# Sheet1.net
KiCad netlist of a schematic drawn in Altium Designer
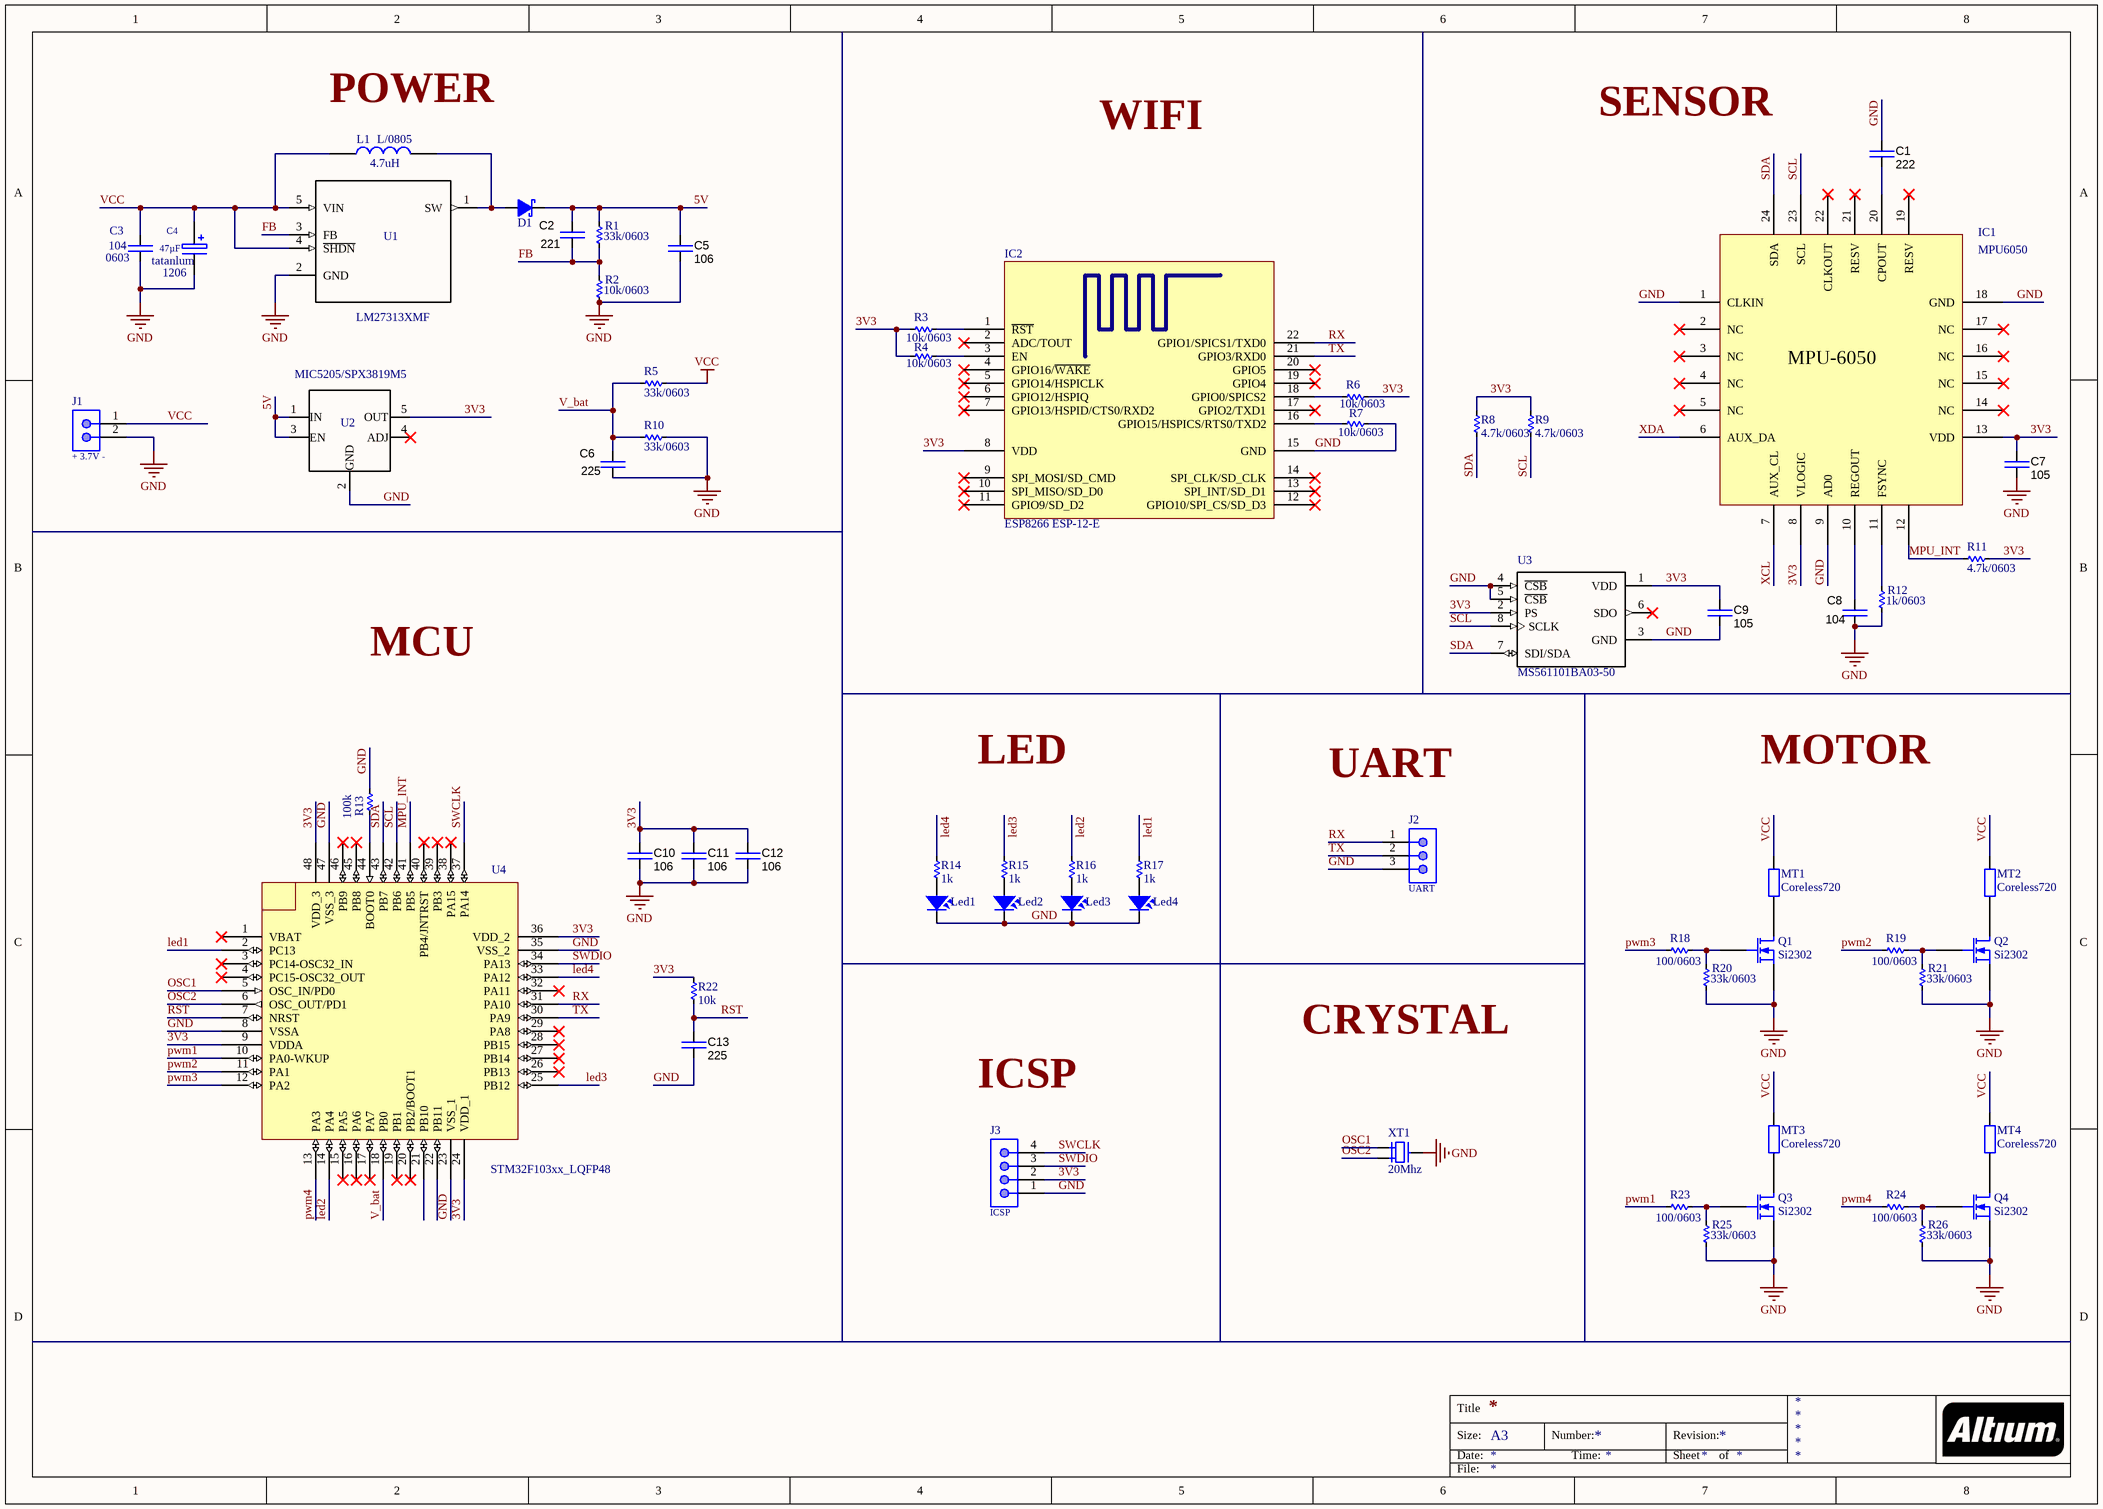
[diagram p0: Sheet1.SchDoc]

(export (version "E")
  (design (tool "Eeschema 10.0.6"))
  (components
    (comp (ref "C1")
      (value "222")
      (footprint "my Library:CAPC1608X90N")
      (description "Capacitor SMD Cer 470nF 10% 16V X7R 0603")
      (fields (field (name "TOLERANCE") "±10%"))
      (libsource (lib "my Library") (part "CAP C_0603"))
    )
    (comp (ref "C2")
      (value "221")
      (footprint "my Library:CAPC1608X90N")
      (description "Capacitor SMD Cer 470nF 10% 16V X7R 0603")
      (fields (field (name "TOLERANCE") "±10%"))
      (libsource (lib "my Library") (part "CAP C_0603"))
    )
    (comp (ref "C3")
      (value "104")
      (footprint "CAPC1608X90N")
      (description "Capacitor SMD 224/0603, Addr:Linhkien69.vn")
      (fields (field (name "PACKAGE / CASE") "0603") (field (name "TOLERANCE") "±10%"))
      (libsource (lib "My library altium") (part "CAP C_0603"))
    )
    (comp (ref "C4")
      (value "tatanlum")
      (footprint "CM_S_1206")
      (description "Tatalium SMD 47uf/1206, Addr:Linhkien69.vn")
      (fields (field (name "ALTIUM_UNNAMED_1") "47µF") (field (name "SIZE") "1206"))
      (libsource (lib "My library altium") (part "CAP Tatalium"))
    )
    (comp (ref "C5")
      (value "106")
      (footprint "my Library:CAPC1608X90N")
      (description "Capacitor SMD Cer 470nF 10% 16V X7R 0603")
      (fields (field (name "TOLERANCE") "±10%"))
      (libsource (lib "my Library") (part "CAP C_0603"))
    )
    (comp (ref "C6")
      (value "225")
      (footprint "my Library:CAPC1608X90N")
      (description "Capacitor SMD Cer 470nF 10% 16V X7R 0603")
      (fields (field (name "TOLERANCE") "±10%"))
      (libsource (lib "my Library") (part "CAP C_0603"))
    )
    (comp (ref "C7")
      (value "105")
      (footprint "my Library:CAPC1608X90N")
      (description "Capacitor SMD Cer 470nF 10% 16V X7R 0603")
      (fields (field (name "TOLERANCE") "±10%"))
      (libsource (lib "my Library") (part "CAP C_0603"))
    )
    (comp (ref "C8")
      (value "104")
      (footprint "my Library:CAPC1608X90N")
      (description "Capacitor SMD Cer 470nF 10% 16V X7R 0603")
      (fields (field (name "TOLERANCE") "±10%"))
      (libsource (lib "my Library") (part "CAP C_0603"))
    )
    (comp (ref "C9")
      (value "105")
      (footprint "my Library:CAPC1608X90N")
      (description "Capacitor SMD Cer 470nF 10% 16V X7R 0603")
      (fields (field (name "TOLERANCE") "±10%"))
      (libsource (lib "my Library") (part "CAP C_0603"))
    )
    (comp (ref "C10")
      (value "106")
      (footprint "my Library:CAPC1608X90N")
      (description "Capacitor SMD Cer 470nF 10% 16V X7R 0603")
      (fields (field (name "TOLERANCE") "±10%"))
      (libsource (lib "my Library") (part "CAP C_0603"))
    )
    (comp (ref "C11")
      (value "106")
      (footprint "my Library:CAPC1608X90N")
      (description "Capacitor SMD Cer 470nF 10% 16V X7R 0603")
      (fields (field (name "TOLERANCE") "±10%"))
      (libsource (lib "my Library") (part "CAP C_0603"))
    )
    (comp (ref "C12")
      (value "106")
      (footprint "my Library:CAPC1608X90N")
      (description "Capacitor SMD Cer 470nF 10% 16V X7R 0603")
      (fields (field (name "TOLERANCE") "±10%"))
      (libsource (lib "my Library") (part "CAP C_0603"))
    )
    (comp (ref "C13")
      (value "225")
      (footprint "my Library:CAPC1608X90N")
      (description "Capacitor SMD Cer 470nF 10% 16V X7R 0603")
      (fields (field (name "TOLERANCE") "±10%"))
      (libsource (lib "my Library") (part "CAP C_0603"))
    )
    (comp (ref "D1")
      (value "Diode  Schottky 1N5819")
      (footprint "DO-214AC")
      (description "Diode SS24 SMD 0805, Addr:Linhkien69.vn")
      (libsource (lib "My library altium") (part "Diode  Schottky 1N5819"))
    )
    (comp (ref "IC1")
      (value "MPU6050")
      (footprint "MPU6050")
      (description "Addr:Banlinhkien.vn")
      (libsource (lib "My library altium") (part "MPU6050"))
    )
    (comp (ref "IC2")
      (value "ESP8266 ESP-12-E")
      (footprint "ESP8266:ESP8266 ESP-12-E")
      (libsource (lib "ESP8266") (part "ESP8266 ESP-12-E"))
    )
    (comp (ref "J1")
      (value "+ 3.7V -")
      (footprint "62000211121")
      (description "WR-PHD Pin Header, THT, pitch 2mm, Single Row, Vertical, 2pin")
      (fields (field (name "PART NUMBER") "62000211121") (field (name "PUBLISHER") "Wurth Elektronik"))
      (libsource (lib "o155175v243 Altium_WR-PHD (rev19a)") (part "62000211121"))
    )
    (comp (ref "J2")
      (value "UART")
      (footprint "62000311121")
      (description "WR-PHD Pin Header, THT, pitch 2mm, Single Row, Vertical, 3pin")
      (fields (field (name "PART NUMBER") "62000311121") (field (name "PUBLISHER") "Wurth Elektronik"))
      (libsource (lib "o155175v243 Altium_WR-PHD (rev19a)") (part "62000311121"))
    )
    (comp (ref "J3")
      (value "ICSP")
      (footprint "62000411121")
      (description "WR-PHD Pin Header, THT, pitch 2mm, Single Row, Vertical, 4pin")
      (fields (field (name "PART NUMBER") "62000411121") (field (name "PUBLISHER") "Wurth Elektronik"))
      (libsource (lib "o155175v243 Altium_WR-PHD (rev19a)") (part "62000411121"))
    )
    (comp (ref "L1")
      (value "L/0805")
      (footprint "SM-IND-0805")
      (description "Inductor SMD 4.7uH/0805, Addr:Linhkien69.vn")
      (fields (field (name "ALTIUM_VALUE") "4.7uH"))
      (libsource (lib "My library altium") (part "Inductor Iron"))
    )
    (comp (ref "Led1")
      (value "LED")
      (footprint "LED-0805-Red")
      (description "LED SMD0805                Addr:Linhkien69.vn")
      (libsource (lib "LIBRARY") (part "LED SMD"))
    )
    (comp (ref "Led2")
      (value "LED")
      (footprint "LED-0805-Red")
      (description "LED SMD0805                Addr:Linhkien69.vn")
      (libsource (lib "LIBRARY") (part "LED SMD"))
    )
    (comp (ref "Led3")
      (value "LED")
      (footprint "LED-0805-Red")
      (description "LED SMD0805                Addr:Linhkien69.vn")
      (libsource (lib "LIBRARY") (part "LED SMD"))
    )
    (comp (ref "Led4")
      (value "LED")
      (footprint "LED-0805-Red")
      (description "LED SMD0805                Addr:Linhkien69.vn")
      (libsource (lib "LIBRARY") (part "LED SMD"))
    )
    (comp (ref "MT1")
      (value "Coreless720")
      (footprint "SM-0805")
      (description "Resistor SMD")
      (libsource (lib "syhaunguyen") (part "RM"))
    )
    (comp (ref "MT2")
      (value "Coreless720")
      (footprint "SM-0805")
      (description "Resistor SMD")
      (libsource (lib "syhaunguyen") (part "RM"))
    )
    (comp (ref "MT3")
      (value "Coreless720")
      (footprint "SM-0805")
      (description "Resistor SMD")
      (libsource (lib "syhaunguyen") (part "RM"))
    )
    (comp (ref "MT4")
      (value "Coreless720")
      (footprint "SM-0805")
      (description "Resistor SMD")
      (libsource (lib "syhaunguyen") (part "RM"))
    )
    (comp (ref "Q1")
      (value "Si2302")
      (footprint "SOT23")
      (description "Transistor SMD            Addr:Banlinhkien.vn")
      (fields (field (name "PUBLISHER") "Altium Limited"))
      (libsource (lib "My library altium") (part "Si2302DS"))
    )
    (comp (ref "Q2")
      (value "Si2302")
      (footprint "SOT23")
      (description "Transistor SMD            Addr:Banlinhkien.vn")
      (fields (field (name "PUBLISHER") "Altium Limited"))
      (libsource (lib "My library altium") (part "Si2302DS"))
    )
    (comp (ref "Q3")
      (value "Si2302")
      (footprint "SOT23")
      (description "Transistor SMD            Addr:Banlinhkien.vn")
      (fields (field (name "PUBLISHER") "Altium Limited"))
      (libsource (lib "My library altium") (part "Si2302DS"))
    )
    (comp (ref "Q4")
      (value "Si2302")
      (footprint "SOT23")
      (description "Transistor SMD            Addr:Banlinhkien.vn")
      (fields (field (name "PUBLISHER") "Altium Limited"))
      (libsource (lib "My library altium") (part "Si2302DS"))
    )
    (comp (ref "R1")
      (value "33k/0603")
      (footprint "RES-SMD-0603")
      (description "Resistor SMD 33k/0603, Addr:Linhkien69.vn")
      (fields
        (field (name "MANUFACTURER") "Generic Components")
        (field (name "PUBLISHER") "Altium Hobart Technology Centre")
      )
      (libsource (lib "LIBRARY") (part "Res-SMD"))
    )
    (comp (ref "R2")
      (value "10k/0603")
      (footprint "RES-SMD-0603")
      (description "Resistor SMD 10k/0603, Addr:Linhkien69.vn")
      (fields
        (field (name "MANUFACTURER") "Generic Components")
        (field (name "PUBLISHER") "Altium Hobart Technology Centre")
      )
      (libsource (lib "LIBRARY") (part "Res-SMD"))
    )
    (comp (ref "R3")
      (value "10k/0603")
      (footprint "RES-SMD-0603")
      (description "Resistor SMD 4.7k/0603, Addr:Linhkien69.vn")
      (fields
        (field (name "MANUFACTURER") "Generic Components")
        (field (name "PUBLISHER") "Altium Hobart Technology Centre")
      )
      (libsource (lib "LIBRARY") (part "Res-SMD"))
    )
    (comp (ref "R4")
      (value "10k/0603")
      (footprint "RES-SMD-0603")
      (description "Resistor SMD 4.7k/0603, Addr:Linhkien69.vn")
      (fields
        (field (name "MANUFACTURER") "Generic Components")
        (field (name "PUBLISHER") "Altium Hobart Technology Centre")
      )
      (libsource (lib "LIBRARY") (part "Res-SMD"))
    )
    (comp (ref "R5")
      (value "33k/0603")
      (footprint "RES-SMD-0603")
      (description "Resistor SMD 33k/0603, Addr:Linhkien69.vn")
      (fields
        (field (name "MANUFACTURER") "Generic Components")
        (field (name "PUBLISHER") "Altium Hobart Technology Centre")
      )
      (libsource (lib "LIBRARY") (part "Res-SMD"))
    )
    (comp (ref "R6")
      (value "10k/0603")
      (footprint "RES-SMD-0603")
      (description "Resistor SMD 4.7k/0603, Addr:Linhkien69.vn")
      (fields
        (field (name "MANUFACTURER") "Generic Components")
        (field (name "PUBLISHER") "Altium Hobart Technology Centre")
      )
      (libsource (lib "LIBRARY") (part "Res-SMD"))
    )
    (comp (ref "R7")
      (value "10k/0603")
      (footprint "RES-SMD-0603")
      (description "Resistor SMD 4.7k/0603, Addr:Linhkien69.vn")
      (fields
        (field (name "MANUFACTURER") "Generic Components")
        (field (name "PUBLISHER") "Altium Hobart Technology Centre")
      )
      (libsource (lib "LIBRARY") (part "Res-SMD"))
    )
    (comp (ref "R8")
      (value "4.7k/0603")
      (footprint "RES-SMD-0603")
      (description "Resistor SMD 4.7k/0603, Addr:Linhkien69.vn")
      (fields
        (field (name "MANUFACTURER") "Generic Components")
        (field (name "PUBLISHER") "Altium Hobart Technology Centre")
      )
      (libsource (lib "LIBRARY") (part "Res-SMD"))
    )
    (comp (ref "R9")
      (value "4.7k/0603")
      (footprint "RES-SMD-0603")
      (description "Resistor SMD 4.7k/0603, Addr:Linhkien69.vn")
      (fields
        (field (name "MANUFACTURER") "Generic Components")
        (field (name "PUBLISHER") "Altium Hobart Technology Centre")
      )
      (libsource (lib "LIBRARY") (part "Res-SMD"))
    )
    (comp (ref "R10")
      (value "33k/0603")
      (footprint "RES-SMD-0603")
      (description "Resistor SMD 33k/0603, Addr:Linhkien69.vn")
      (fields
        (field (name "MANUFACTURER") "Generic Components")
        (field (name "PUBLISHER") "Altium Hobart Technology Centre")
      )
      (libsource (lib "LIBRARY") (part "Res-SMD"))
    )
    (comp (ref "R11")
      (value "4.7k/0603")
      (footprint "RES-SMD-0603")
      (description "Resistor SMD 4.7k/0603, Addr:Linhkien69.vn")
      (fields
        (field (name "MANUFACTURER") "Generic Components")
        (field (name "PUBLISHER") "Altium Hobart Technology Centre")
      )
      (libsource (lib "LIBRARY") (part "Res-SMD"))
    )
    (comp (ref "R12")
      (value "1k/0603")
      (footprint "RES-SMD-0603")
      (description "Resistor SMD 1k/0603, Addr:Linhkien69.vn")
      (fields
        (field (name "MANUFACTURER") "Generic Components")
        (field (name "PUBLISHER") "Altium Hobart Technology Centre")
      )
      (libsource (lib "LIBRARY") (part "Res-SMD"))
    )
    (comp (ref "R13")
      (value "100k")
      (footprint "RES-SMD-0603")
      (description "Resistor")
      (fields
        (field (name "MANUFACTURER") "Generic Components")
        (field (name "PUBLISHER") "Altium Hobart Technology Centre")
      )
      (libsource (lib "LIBRARY") (part "Res-SMD"))
    )
    (comp (ref "R14")
      (value "1k")
      (footprint "RES-SMD-0603")
      (description "Resistor SMD 1k/0603, Addr:Linhkien69.vn")
      (fields
        (field (name "MANUFACTURER") "Generic Components")
        (field (name "PUBLISHER") "Altium Hobart Technology Centre")
      )
      (libsource (lib "LIBRARY") (part "Res-SMD"))
    )
    (comp (ref "R15")
      (value "1k")
      (footprint "RES-SMD-0603")
      (description "Resistor SMD 1k/0603, Addr:Linhkien69.vn")
      (fields
        (field (name "MANUFACTURER") "Generic Components")
        (field (name "PUBLISHER") "Altium Hobart Technology Centre")
      )
      (libsource (lib "LIBRARY") (part "Res-SMD"))
    )
    (comp (ref "R16")
      (value "1k")
      (footprint "RES-SMD-0603")
      (description "Resistor SMD 1k/0603, Addr:Linhkien69.vn")
      (fields
        (field (name "MANUFACTURER") "Generic Components")
        (field (name "PUBLISHER") "Altium Hobart Technology Centre")
      )
      (libsource (lib "LIBRARY") (part "Res-SMD"))
    )
    (comp (ref "R17")
      (value "1k")
      (footprint "RES-SMD-0603")
      (description "Resistor SMD 1k/0603, Addr:Linhkien69.vn")
      (fields
        (field (name "MANUFACTURER") "Generic Components")
        (field (name "PUBLISHER") "Altium Hobart Technology Centre")
      )
      (libsource (lib "LIBRARY") (part "Res-SMD"))
    )
    (comp (ref "R18")
      (value "100/0603")
      (footprint "RES-SMD-0603")
      (description "Resistor SMD 33k/0603, Addr:Linhkien69.vn")
      (fields
        (field (name "MANUFACTURER") "Generic Components")
        (field (name "PUBLISHER") "Altium Hobart Technology Centre")
      )
      (libsource (lib "LIBRARY") (part "Res-SMD"))
    )
    (comp (ref "R19")
      (value "100/0603")
      (footprint "RES-SMD-0603")
      (description "Resistor SMD 33k/0603, Addr:Linhkien69.vn")
      (fields
        (field (name "MANUFACTURER") "Generic Components")
        (field (name "PUBLISHER") "Altium Hobart Technology Centre")
      )
      (libsource (lib "LIBRARY") (part "Res-SMD"))
    )
    (comp (ref "R20")
      (value "33k/0603")
      (footprint "RES-SMD-0603")
      (description "Resistor SMD 33k/0603, Addr:Linhkien69.vn")
      (fields
        (field (name "MANUFACTURER") "Generic Components")
        (field (name "PUBLISHER") "Altium Hobart Technology Centre")
      )
      (libsource (lib "LIBRARY") (part "Res-SMD"))
    )
    (comp (ref "R21")
      (value "33k/0603")
      (footprint "RES-SMD-0603")
      (description "Resistor SMD 33k/0603, Addr:Linhkien69.vn")
      (fields
        (field (name "MANUFACTURER") "Generic Components")
        (field (name "PUBLISHER") "Altium Hobart Technology Centre")
      )
      (libsource (lib "LIBRARY") (part "Res-SMD"))
    )
    (comp (ref "R22")
      (value "10k")
      (footprint "RES-SMD-0603")
      (description "Resistor")
      (fields
        (field (name "MANUFACTURER") "Generic Components")
        (field (name "PUBLISHER") "Altium Hobart Technology Centre")
      )
      (libsource (lib "LIBRARY") (part "Res-SMD"))
    )
    (comp (ref "R23")
      (value "100/0603")
      (footprint "RES-SMD-0603")
      (description "Resistor SMD 33k/0603, Addr:Linhkien69.vn")
      (fields
        (field (name "MANUFACTURER") "Generic Components")
        (field (name "PUBLISHER") "Altium Hobart Technology Centre")
      )
      (libsource (lib "LIBRARY") (part "Res-SMD"))
    )
    (comp (ref "R24")
      (value "100/0603")
      (footprint "RES-SMD-0603")
      (description "Resistor SMD 33k/0603, Addr:Linhkien69.vn")
      (fields
        (field (name "MANUFACTURER") "Generic Components")
        (field (name "PUBLISHER") "Altium Hobart Technology Centre")
      )
      (libsource (lib "LIBRARY") (part "Res-SMD"))
    )
    (comp (ref "R25")
      (value "33k/0603")
      (footprint "RES-SMD-0603")
      (description "Resistor SMD 33k/0603, Addr:Linhkien69.vn")
      (fields
        (field (name "MANUFACTURER") "Generic Components")
        (field (name "PUBLISHER") "Altium Hobart Technology Centre")
      )
      (libsource (lib "LIBRARY") (part "Res-SMD"))
    )
    (comp (ref "R26")
      (value "33k/0603")
      (footprint "RES-SMD-0603")
      (description "Resistor SMD 33k/0603, Addr:Linhkien69.vn")
      (fields
        (field (name "MANUFACTURER") "Generic Components")
        (field (name "PUBLISHER") "Altium Hobart Technology Centre")
      )
      (libsource (lib "LIBRARY") (part "Res-SMD"))
    )
    (comp (ref "U1")
      (value "LM27313XMF")
      (footprint "SOT95P285X120-5N")
      (description "Boost SMD/SOT95,  Addr:Banlinhkien.vn")
      (fields (field (name "MP") "LM27313XMF/NOPB") (field (name "MF") "Texas Instruments"))
      (libsource (lib "LM27313XMF") (part "LM27313XMF"))
    )
    (comp (ref "U2")
      (value "MIC5205/SPX3819M5")
      (footprint "SOT-23-5")
      (description "3.3V SMD/SOT23,    Addr:Banlinhkien.vn")
      (fields (field (name "MP") "MIC5205-3.3YM5 TR") (field (name "MF") "Micrel"))
      (libsource (lib "PMIC-MIC5205-3.3YMSTR_SOT23-5_") (part "PMIC-MIC5205-3.3YMSTR(SOT23-5)"))
    )
    (comp (ref "U3")
      (value "MS561101BA03-50")
      (footprint "SON125P500X300X100-8N")
      (description "Addr:Banlinhkien.vn")
      (fields (field (name "MF") "TE Connectivity"))
      (libsource (lib "MS561101BA03-50") (part "MS561101BA03-50"))
    )
    (comp (ref "U4")
      (value "STM32F103xx_LQFP48")
      (footprint "STM32_LQPF48")
      (description "STM32 ARM-based 32-bit MCU with 64 Kbytes Flash, 48-pin LQFP, Industrial Temperature")
      (fields (field (name "PUBLISHER") "Altium Limited"))
      (libsource (lib "My library altium") (part "STM32F103xx_LQFP48"))
    )
    (comp (ref "XT1")
      (value "20Mhz")
      (footprint "CRYSTAL CSTCE20M0V53-R0")
      (description "Crystal For all Crystal 2pin.")
      (libsource (lib "My library altium") (part "CRYSTAL 3 Chan"))
    )
  )
  (nets
    (net (code "1") (name "/3V3") (class "Default")
      (node (ref "C10") (pin "2") (pintype "passive"))
      (node (ref "C11") (pin "2") (pintype "passive"))
      (node (ref "C12") (pin "2") (pintype "passive"))
      (node (ref "C7") (pin "2") (pintype "passive"))
      (node (ref "C9") (pin "2") (pintype "passive"))
      (node (ref "IC1") (pin "13") (pinfunction "VDD_13") (pintype "passive"))
      (node (ref "IC1") (pin "8") (pinfunction "VLOGIC_8") (pintype "passive"))
      (node (ref "IC2") (pin "8") (pinfunction "VDD_8") (pintype "passive"))
      (node (ref "J3") (pin "2") (pinfunction "2_2") (pintype "passive"))
      (node (ref "R11") (pin "2") (pinfunction "2_2") (pintype "passive"))
      (node (ref "R22") (pin "2") (pinfunction "2_2") (pintype "passive"))
      (node (ref "R3") (pin "2") (pinfunction "2_2") (pintype "passive"))
      (node (ref "R4") (pin "2") (pinfunction "2_2") (pintype "passive"))
      (node (ref "R6") (pin "1") (pinfunction "1_1") (pintype "passive"))
      (node (ref "R8") (pin "2") (pinfunction "2_2") (pintype "passive"))
      (node (ref "R9") (pin "2") (pinfunction "2_2") (pintype "passive"))
      (node (ref "U2") (pin "5") (pinfunction "OUT_5") (pintype "bidirectional"))
      (node (ref "U3") (pin "1") (pinfunction "VDD_1") (pintype "power_in"))
      (node (ref "U3") (pin "2") (pinfunction "PS_2") (pintype "input"))
      (node (ref "U4") (pin "24") (pinfunction "VDD_1_24") (pintype "power_in"))
      (node (ref "U4") (pin "36") (pinfunction "VDD_2_36") (pintype "power_in"))
      (node (ref "U4") (pin "48") (pinfunction "VDD_3_48") (pintype "power_in"))
      (node (ref "U4") (pin "9") (pinfunction "VDDA_9") (pintype "power_in"))
    )
    (net (code "2") (name "/5V") (class "Default")
      (node (ref "C2") (pin "2") (pintype "passive"))
      (node (ref "C5") (pin "2") (pintype "passive"))
      (node (ref "D1") (pin "K") (pinfunction "K_K") (pintype "passive"))
      (node (ref "R1") (pin "1") (pinfunction "1_1") (pintype "passive"))
      (node (ref "U2") (pin "1") (pinfunction "IN_1") (pintype "bidirectional"))
      (node (ref "U2") (pin "3") (pinfunction "EN_3") (pintype "bidirectional"))
    )
    (net (code "3") (name "/FB") (class "Default")
      (node (ref "C2") (pin "1") (pintype "passive"))
      (node (ref "R1") (pin "2") (pinfunction "2_2") (pintype "passive"))
      (node (ref "R2") (pin "1") (pinfunction "1_1") (pintype "passive"))
      (node (ref "U1") (pin "3") (pinfunction "FB_3") (pintype "input"))
    )
    (net (code "4") (name "/MPU_INT") (class "Default")
      (node (ref "IC1") (pin "12") (pintype "passive"))
      (node (ref "R11") (pin "1") (pinfunction "1_1") (pintype "passive"))
      (node (ref "U4") (pin "41") (pinfunction "PB5_41") (pintype "bidirectional"))
    )
    (net (code "5") (name "/OSC1") (class "Default")
      (node (ref "U4") (pin "5") (pinfunction "OSC_IN/PD0_5") (pintype "input"))
      (node (ref "XT1") (pin "1") (pinfunction "1_1") (pintype "passive"))
    )
    (net (code "6") (name "/OSC2") (class "Default")
      (node (ref "U4") (pin "6") (pinfunction "OSC_OUT/PD1_6") (pintype "output"))
      (node (ref "XT1") (pin "3") (pinfunction "3_3") (pintype "passive"))
    )
    (net (code "7") (name "/RST") (class "Default")
      (node (ref "C13") (pin "2") (pintype "passive"))
      (node (ref "R22") (pin "1") (pinfunction "1_1") (pintype "passive"))
      (node (ref "U4") (pin "7") (pinfunction "NRST_7") (pintype "bidirectional"))
    )
    (net (code "8") (name "/RX") (class "Default")
      (node (ref "IC2") (pin "22") (pinfunction "GPIO1/SPICS1/TXD0_22") (pintype "passive"))
      (node (ref "J2") (pin "1") (pinfunction "1_1") (pintype "passive"))
      (node (ref "U4") (pin "31") (pinfunction "PA10_31") (pintype "bidirectional"))
    )
    (net (code "9") (name "/SCL") (class "Default")
      (node (ref "IC1") (pin "23") (pinfunction "SCL_23") (pintype "passive"))
      (node (ref "R9") (pin "1") (pinfunction "1_1") (pintype "passive"))
      (node (ref "U3") (pin "8") (pinfunction "SCLK_8") (pintype "input"))
      (node (ref "U4") (pin "42") (pinfunction "PB6_42") (pintype "bidirectional"))
    )
    (net (code "10") (name "/SDA") (class "Default")
      (node (ref "IC1") (pin "24") (pinfunction "SDA_24") (pintype "passive"))
      (node (ref "R8") (pin "1") (pinfunction "1_1") (pintype "passive"))
      (node (ref "U3") (pin "7") (pinfunction "SDI/SDA_7") (pintype "bidirectional"))
      (node (ref "U4") (pin "43") (pinfunction "PB7_43") (pintype "bidirectional"))
    )
    (net (code "11") (name "/SWCLK") (class "Default")
      (node (ref "J3") (pin "4") (pinfunction "4_4") (pintype "passive"))
      (node (ref "U4") (pin "37") (pinfunction "PA14_37") (pintype "bidirectional"))
    )
    (net (code "12") (name "/SWDIO") (class "Default")
      (node (ref "J3") (pin "3") (pinfunction "3_3") (pintype "passive"))
      (node (ref "U4") (pin "34") (pinfunction "PA13_34") (pintype "bidirectional"))
    )
    (net (code "13") (name "/TX") (class "Default")
      (node (ref "IC2") (pin "21") (pinfunction "GPIO3/RXD0_21") (pintype "passive"))
      (node (ref "J2") (pin "2") (pinfunction "2_2") (pintype "passive"))
      (node (ref "U4") (pin "30") (pinfunction "PA9_30") (pintype "bidirectional"))
    )
    (net (code "14") (name "/V_bat") (class "Default")
      (node (ref "C6") (pin "2") (pintype "passive"))
      (node (ref "R10") (pin "1") (pinfunction "1_1") (pintype "passive"))
      (node (ref "R5") (pin "1") (pinfunction "1_1") (pintype "passive"))
      (node (ref "U4") (pin "18") (pinfunction "PB0_18") (pintype "bidirectional"))
    )
    (net (code "15") (name "/XCL") (class "Default")
      (node (ref "IC1") (pin "7") (pinfunction "AUX_CL_7") (pintype "passive"))
    )
    (net (code "16") (name "/XDA") (class "Default")
      (node (ref "IC1") (pin "6") (pinfunction "AUX_DA_6") (pintype "passive"))
    )
    (net (code "17") (name "/led1") (class "Default")
      (node (ref "R17") (pin "2") (pinfunction "2_2") (pintype "passive"))
      (node (ref "U4") (pin "2") (pinfunction "PC13_2") (pintype "bidirectional"))
    )
    (net (code "18") (name "/led2") (class "Default")
      (node (ref "R16") (pin "2") (pinfunction "2_2") (pintype "passive"))
      (node (ref "U4") (pin "14") (pinfunction "PA4_14") (pintype "bidirectional"))
    )
    (net (code "19") (name "/led3") (class "Default")
      (node (ref "R15") (pin "2") (pinfunction "2_2") (pintype "passive"))
      (node (ref "U4") (pin "25") (pinfunction "PB12_25") (pintype "bidirectional"))
    )
    (net (code "20") (name "/led4") (class "Default")
      (node (ref "R14") (pin "2") (pinfunction "2_2") (pintype "passive"))
      (node (ref "U4") (pin "33") (pinfunction "PA12_33") (pintype "bidirectional"))
    )
    (net (code "21") (name "/pwm1") (class "Default")
      (node (ref "R23") (pin "1") (pinfunction "1_1") (pintype "passive"))
      (node (ref "U4") (pin "10") (pinfunction "PA0-WKUP_10") (pintype "bidirectional"))
    )
    (net (code "22") (name "/pwm2") (class "Default")
      (node (ref "R19") (pin "1") (pinfunction "1_1") (pintype "passive"))
      (node (ref "U4") (pin "11") (pinfunction "PA1_11") (pintype "bidirectional"))
    )
    (net (code "23") (name "/pwm3") (class "Default")
      (node (ref "R18") (pin "1") (pinfunction "1_1") (pintype "passive"))
      (node (ref "U4") (pin "12") (pinfunction "PA2_12") (pintype "bidirectional"))
    )
    (net (code "24") (name "/pwm4") (class "Default")
      (node (ref "R24") (pin "1") (pinfunction "1_1") (pintype "passive"))
      (node (ref "U4") (pin "13") (pinfunction "PA3_13") (pintype "bidirectional"))
    )
    (net (code "25") (name "GND") (class "Default")
      (node (ref "C1") (pin "2") (pintype "passive"))
      (node (ref "C10") (pin "1") (pintype "passive"))
      (node (ref "C11") (pin "1") (pintype "passive"))
      (node (ref "C12") (pin "1") (pintype "passive"))
      (node (ref "C13") (pin "1") (pintype "passive"))
      (node (ref "C3") (pin "1") (pintype "passive"))
      (node (ref "C4") (pin "2") (pintype "passive"))
      (node (ref "C5") (pin "1") (pintype "passive"))
      (node (ref "C6") (pin "1") (pintype "passive"))
      (node (ref "C7") (pin "1") (pintype "passive"))
      (node (ref "C8") (pin "1") (pintype "passive"))
      (node (ref "C9") (pin "1") (pintype "passive"))
      (node (ref "IC1") (pin "1") (pinfunction "CLKIN_1") (pintype "passive"))
      (node (ref "IC1") (pin "18") (pinfunction "GND_18") (pintype "passive"))
      (node (ref "IC1") (pin "9") (pinfunction "AD0_9") (pintype "passive"))
      (node (ref "IC2") (pin "15") (pinfunction "GND_15") (pintype "passive"))
      (node (ref "J1") (pin "2") (pinfunction "2_2") (pintype "passive"))
      (node (ref "J2") (pin "3") (pinfunction "3_3") (pintype "passive"))
      (node (ref "J3") (pin "1") (pinfunction "1_1") (pintype "passive"))
      (node (ref "Led1") (pin "2") (pinfunction "2_2") (pintype "passive"))
      (node (ref "Led2") (pin "2") (pinfunction "2_2") (pintype "passive"))
      (node (ref "Led3") (pin "2") (pinfunction "2_2") (pintype "passive"))
      (node (ref "Led4") (pin "2") (pinfunction "2_2") (pintype "passive"))
      (node (ref "Q1") (pin "2") (pinfunction "S_2") (pintype "passive"))
      (node (ref "Q2") (pin "2") (pinfunction "S_2") (pintype "passive"))
      (node (ref "Q3") (pin "2") (pinfunction "S_2") (pintype "passive"))
      (node (ref "Q4") (pin "2") (pinfunction "S_2") (pintype "passive"))
      (node (ref "R10") (pin "2") (pinfunction "2_2") (pintype "passive"))
      (node (ref "R12") (pin "2") (pinfunction "2_2") (pintype "passive"))
      (node (ref "R13") (pin "2") (pinfunction "2_2") (pintype "passive"))
      (node (ref "R2") (pin "2") (pinfunction "2_2") (pintype "passive"))
      (node (ref "R20") (pin "2") (pinfunction "2_2") (pintype "passive"))
      (node (ref "R21") (pin "2") (pinfunction "2_2") (pintype "passive"))
      (node (ref "R25") (pin "2") (pinfunction "2_2") (pintype "passive"))
      (node (ref "R26") (pin "2") (pinfunction "2_2") (pintype "passive"))
      (node (ref "R7") (pin "1") (pinfunction "1_1") (pintype "passive"))
      (node (ref "U1") (pin "2") (pinfunction "GND_2") (pintype "passive"))
      (node (ref "U2") (pin "2") (pinfunction "GND_2") (pintype "bidirectional"))
      (node (ref "U3") (pin "3") (pinfunction "GND_3") (pintype "power_in"))
      (node (ref "U3") (pin "4") (pinfunction "~{CSB}_4") (pintype "input"))
      (node (ref "U3") (pin "5") (pinfunction "~{CSB}_5") (pintype "input"))
      (node (ref "U4") (pin "23") (pinfunction "VSS_1_23") (pintype "power_in"))
      (node (ref "U4") (pin "35") (pinfunction "VSS_2_35") (pintype "power_in"))
      (node (ref "U4") (pin "47") (pinfunction "VSS_3_47") (pintype "power_in"))
      (node (ref "U4") (pin "8") (pinfunction "VSSA_8") (pintype "power_in"))
      (node (ref "XT1") (pin "2") (pinfunction "2_2") (pintype "passive"))
    )
    (net (code "26") (name "Net-(IC1-CPOUT)") (class "Default")
      (node (ref "C1") (pin "1") (pintype "passive"))
      (node (ref "IC1") (pin "20") (pinfunction "CPOUT_20") (pintype "passive"))
    )
    (net (code "27") (name "Net-(IC1-FSYNC)") (class "Default")
      (node (ref "IC1") (pin "11") (pinfunction "FSYNC_11") (pintype "passive"))
      (node (ref "R12") (pin "1") (pinfunction "1_1") (pintype "passive"))
    )
    (net (code "28") (name "Net-(IC1-REGOUT)") (class "Default")
      (node (ref "C8") (pin "2") (pintype "passive"))
      (node (ref "IC1") (pin "10") (pinfunction "REGOUT_10") (pintype "passive"))
    )
    (net (code "29") (name "Net-(IC2-EN)") (class "Default")
      (node (ref "IC2") (pin "3") (pinfunction "EN_3") (pintype "passive"))
      (node (ref "R4") (pin "1") (pinfunction "1_1") (pintype "passive"))
    )
    (net (code "30") (name "Net-(IC2-GPIO0{slash}SPICS2)") (class "Default")
      (node (ref "IC2") (pin "18") (pinfunction "GPIO0/SPICS2_18") (pintype "passive"))
      (node (ref "R6") (pin "2") (pinfunction "2_2") (pintype "passive"))
    )
    (net (code "31") (name "Net-(IC2-GPIO15{slash}HSPICS{slash}RTS0{slash}TXD2)") (class "Default")
      (node (ref "IC2") (pin "16") (pinfunction "GPIO15/HSPICS/RTS0/TXD2_16") (pintype "passive"))
      (node (ref "R7") (pin "2") (pinfunction "2_2") (pintype "passive"))
    )
    (net (code "32") (name "Net-(IC2-~{RST})") (class "Default")
      (node (ref "IC2") (pin "1") (pinfunction "~{RST}_1") (pintype "passive"))
      (node (ref "R3") (pin "1") (pinfunction "1_1") (pintype "passive"))
    )
    (net (code "33") (name "Net-(Led1-Pad1)") (class "Default")
      (node (ref "Led1") (pin "1") (pinfunction "1_1") (pintype "passive"))
      (node (ref "R14") (pin "1") (pinfunction "1_1") (pintype "passive"))
    )
    (net (code "34") (name "Net-(Led2-Pad1)") (class "Default")
      (node (ref "Led2") (pin "1") (pinfunction "1_1") (pintype "passive"))
      (node (ref "R15") (pin "1") (pinfunction "1_1") (pintype "passive"))
    )
    (net (code "35") (name "Net-(Led3-Pad1)") (class "Default")
      (node (ref "Led3") (pin "1") (pinfunction "1_1") (pintype "passive"))
      (node (ref "R16") (pin "1") (pinfunction "1_1") (pintype "passive"))
    )
    (net (code "36") (name "Net-(Led4-Pad1)") (class "Default")
      (node (ref "Led4") (pin "1") (pinfunction "1_1") (pintype "passive"))
      (node (ref "R17") (pin "1") (pinfunction "1_1") (pintype "passive"))
    )
    (net (code "37") (name "Net-(Q1-D)") (class "Default")
      (node (ref "MT1") (pin "1") (pinfunction "1_1") (pintype "passive"))
      (node (ref "Q1") (pin "3") (pinfunction "D_3") (pintype "passive"))
    )
    (net (code "38") (name "Net-(Q1-G)") (class "Default")
      (node (ref "Q1") (pin "1") (pinfunction "G_1") (pintype "passive"))
      (node (ref "R18") (pin "2") (pinfunction "2_2") (pintype "passive"))
      (node (ref "R20") (pin "1") (pinfunction "1_1") (pintype "passive"))
    )
    (net (code "39") (name "Net-(Q2-D)") (class "Default")
      (node (ref "MT2") (pin "1") (pinfunction "1_1") (pintype "passive"))
      (node (ref "Q2") (pin "3") (pinfunction "D_3") (pintype "passive"))
    )
    (net (code "40") (name "Net-(Q2-G)") (class "Default")
      (node (ref "Q2") (pin "1") (pinfunction "G_1") (pintype "passive"))
      (node (ref "R19") (pin "2") (pinfunction "2_2") (pintype "passive"))
      (node (ref "R21") (pin "1") (pinfunction "1_1") (pintype "passive"))
    )
    (net (code "41") (name "Net-(Q3-D)") (class "Default")
      (node (ref "MT3") (pin "1") (pinfunction "1_1") (pintype "passive"))
      (node (ref "Q3") (pin "3") (pinfunction "D_3") (pintype "passive"))
    )
    (net (code "42") (name "Net-(Q3-G)") (class "Default")
      (node (ref "Q3") (pin "1") (pinfunction "G_1") (pintype "passive"))
      (node (ref "R23") (pin "2") (pinfunction "2_2") (pintype "passive"))
      (node (ref "R25") (pin "1") (pinfunction "1_1") (pintype "passive"))
    )
    (net (code "43") (name "Net-(Q4-D)") (class "Default")
      (node (ref "MT4") (pin "1") (pinfunction "1_1") (pintype "passive"))
      (node (ref "Q4") (pin "3") (pinfunction "D_3") (pintype "passive"))
    )
    (net (code "44") (name "Net-(Q4-G)") (class "Default")
      (node (ref "Q4") (pin "1") (pinfunction "G_1") (pintype "passive"))
      (node (ref "R24") (pin "2") (pinfunction "2_2") (pintype "passive"))
      (node (ref "R26") (pin "1") (pinfunction "1_1") (pintype "passive"))
    )
    (net (code "45") (name "Net-(U1-SW)") (class "Default")
      (node (ref "D1") (pin "A") (pinfunction "A_A") (pintype "passive"))
      (node (ref "L1") (pin "2") (pinfunction "2_2") (pintype "passive"))
      (node (ref "U1") (pin "1") (pinfunction "SW_1") (pintype "output"))
    )
    (net (code "46") (name "Net-(U4-BOOT0)") (class "Default")
      (node (ref "R13") (pin "1") (pinfunction "1_1") (pintype "passive"))
      (node (ref "U4") (pin "44") (pinfunction "BOOT0_44") (pintype "input"))
    )
    (net (code "47") (name "VCC") (class "Default")
      (node (ref "C3") (pin "2") (pintype "passive"))
      (node (ref "C4") (pin "1") (pintype "passive"))
      (node (ref "J1") (pin "1") (pinfunction "1_1") (pintype "passive"))
      (node (ref "L1") (pin "1") (pinfunction "1_1") (pintype "passive"))
      (node (ref "MT1") (pin "2") (pinfunction "2_2") (pintype "passive"))
      (node (ref "MT2") (pin "2") (pinfunction "2_2") (pintype "passive"))
      (node (ref "MT3") (pin "2") (pinfunction "2_2") (pintype "passive"))
      (node (ref "MT4") (pin "2") (pinfunction "2_2") (pintype "passive"))
      (node (ref "R5") (pin "2") (pinfunction "2_2") (pintype "passive"))
      (node (ref "U1") (pin "4") (pinfunction "~{SHDN}_4") (pintype "input"))
      (node (ref "U1") (pin "5") (pinfunction "VIN_5") (pintype "input"))
    )
    (net (code "48") (name "unconnected-(IC1-CLKOUT-Pad22)") (class "Default")
      (node (ref "IC1") (pin "22") (pinfunction "CLKOUT_22") (pintype "passive+no_connect"))
    )
    (net (code "49") (name "unconnected-(IC1-NC-Pad2)") (class "Default")
      (node (ref "IC1") (pin "2") (pinfunction "NC_2") (pintype "passive+no_connect"))
    )
    (net (code "50") (name "unconnected-(IC1-NC-Pad3)") (class "Default")
      (node (ref "IC1") (pin "3") (pinfunction "NC_3") (pintype "passive+no_connect"))
    )
    (net (code "51") (name "unconnected-(IC1-NC-Pad4)") (class "Default")
      (node (ref "IC1") (pin "4") (pinfunction "NC_4") (pintype "passive+no_connect"))
    )
    (net (code "52") (name "unconnected-(IC1-NC-Pad5)") (class "Default")
      (node (ref "IC1") (pin "5") (pinfunction "NC_5") (pintype "passive+no_connect"))
    )
    (net (code "53") (name "unconnected-(IC1-NC-Pad14)") (class "Default")
      (node (ref "IC1") (pin "14") (pinfunction "NC_14") (pintype "passive+no_connect"))
    )
    (net (code "54") (name "unconnected-(IC1-NC-Pad15)") (class "Default")
      (node (ref "IC1") (pin "15") (pinfunction "NC_15") (pintype "passive+no_connect"))
    )
    (net (code "55") (name "unconnected-(IC1-NC-Pad16)") (class "Default")
      (node (ref "IC1") (pin "16") (pinfunction "NC_16") (pintype "passive+no_connect"))
    )
    (net (code "56") (name "unconnected-(IC1-NC-Pad17)") (class "Default")
      (node (ref "IC1") (pin "17") (pinfunction "NC_17") (pintype "passive+no_connect"))
    )
    (net (code "57") (name "unconnected-(IC1-RESV-Pad19)") (class "Default")
      (node (ref "IC1") (pin "19") (pinfunction "RESV_19") (pintype "passive+no_connect"))
    )
    (net (code "58") (name "unconnected-(IC1-RESV-Pad21)") (class "Default")
      (node (ref "IC1") (pin "21") (pinfunction "RESV_21") (pintype "passive+no_connect"))
    )
    (net (code "59") (name "unconnected-(IC2-ADC{slash}TOUT-Pad2)") (class "Default")
      (node (ref "IC2") (pin "2") (pinfunction "ADC/TOUT_2") (pintype "passive+no_connect"))
    )
    (net (code "60") (name "unconnected-(IC2-GPIO2{slash}TXD1-Pad17)") (class "Default")
      (node (ref "IC2") (pin "17") (pinfunction "GPIO2/TXD1_17") (pintype "passive+no_connect"))
    )
    (net (code "61") (name "unconnected-(IC2-GPIO4-Pad19)") (class "Default")
      (node (ref "IC2") (pin "19") (pinfunction "GPIO4_19") (pintype "passive+no_connect"))
    )
    (net (code "62") (name "unconnected-(IC2-GPIO5-Pad20)") (class "Default")
      (node (ref "IC2") (pin "20") (pinfunction "GPIO5_20") (pintype "passive+no_connect"))
    )
    (net (code "63") (name "unconnected-(IC2-GPIO9{slash}SD_D2-Pad11)") (class "Default")
      (node (ref "IC2") (pin "11") (pinfunction "GPIO9/SD_D2_11") (pintype "passive+no_connect"))
    )
    (net (code "64") (name "unconnected-(IC2-GPIO10{slash}SPI_CS{slash}SD_D3-Pad12)") (class "Default")
      (node (ref "IC2") (pin "12") (pinfunction "GPIO10/SPI_CS/SD_D3_12") (pintype "passive+no_connect"))
    )
    (net (code "65") (name "unconnected-(IC2-GPIO12{slash}HSPIQ-Pad6)") (class "Default")
      (node (ref "IC2") (pin "6") (pinfunction "GPIO12/HSPIQ_6") (pintype "passive+no_connect"))
    )
    (net (code "66") (name "unconnected-(IC2-GPIO13{slash}HSPID{slash}CTS0{slash}RXD2-Pad7)") (class "Default")
      (node (ref "IC2") (pin "7") (pinfunction "GPIO13/HSPID/CTS0/RXD2_7") (pintype "passive+no_connect"))
    )
    (net (code "67") (name "unconnected-(IC2-GPIO14{slash}HSPICLK-Pad5)") (class "Default")
      (node (ref "IC2") (pin "5") (pinfunction "GPIO14/HSPICLK_5") (pintype "passive+no_connect"))
    )
    (net (code "68") (name "unconnected-(IC2-GPIO16{slash}~{WAKE}-Pad4)") (class "Default")
      (node (ref "IC2") (pin "4") (pinfunction "GPIO16/~{WAKE}_4") (pintype "passive+no_connect"))
    )
    (net (code "69") (name "unconnected-(IC2-SPI_CLK{slash}SD_CLK-Pad14)") (class "Default")
      (node (ref "IC2") (pin "14") (pinfunction "SPI_CLK/SD_CLK_14") (pintype "passive+no_connect"))
    )
    (net (code "70") (name "unconnected-(IC2-SPI_INT{slash}SD_D1-Pad13)") (class "Default")
      (node (ref "IC2") (pin "13") (pinfunction "SPI_INT/SD_D1_13") (pintype "passive+no_connect"))
    )
    (net (code "71") (name "unconnected-(IC2-SPI_MISO{slash}SD_D0-Pad10)") (class "Default")
      (node (ref "IC2") (pin "10") (pinfunction "SPI_MISO/SD_D0_10") (pintype "passive+no_connect"))
    )
    (net (code "72") (name "unconnected-(IC2-SPI_MOSI{slash}SD_CMD-Pad9)") (class "Default")
      (node (ref "IC2") (pin "9") (pinfunction "SPI_MOSI/SD_CMD_9") (pintype "passive+no_connect"))
    )
    (net (code "73") (name "unconnected-(U2-ADJ-Pad4)") (class "Default")
      (node (ref "U2") (pin "4") (pinfunction "ADJ_4") (pintype "bidirectional"))
    )
    (net (code "74") (name "unconnected-(U3-SDO-Pad6)") (class "Default")
      (node (ref "U3") (pin "6") (pinfunction "SDO_6") (pintype "output+no_connect"))
    )
    (net (code "75") (name "unconnected-(U4-PA5-Pad15)") (class "Default")
      (node (ref "U4") (pin "15") (pinfunction "PA5_15") (pintype "bidirectional+no_connect"))
    )
    (net (code "76") (name "unconnected-(U4-PA6-Pad16)") (class "Default")
      (node (ref "U4") (pin "16") (pinfunction "PA6_16") (pintype "bidirectional+no_connect"))
    )
    (net (code "77") (name "unconnected-(U4-PA7-Pad17)") (class "Default")
      (node (ref "U4") (pin "17") (pinfunction "PA7_17") (pintype "bidirectional+no_connect"))
    )
    (net (code "78") (name "unconnected-(U4-PA8-Pad29)") (class "Default")
      (node (ref "U4") (pin "29") (pinfunction "PA8_29") (pintype "bidirectional+no_connect"))
    )
    (net (code "79") (name "unconnected-(U4-PA11-Pad32)") (class "Default")
      (node (ref "U4") (pin "32") (pinfunction "PA11_32") (pintype "bidirectional+no_connect"))
    )
    (net (code "80") (name "unconnected-(U4-PA15-Pad38)") (class "Default")
      (node (ref "U4") (pin "38") (pinfunction "PA15_38") (pintype "bidirectional+no_connect"))
    )
    (net (code "81") (name "unconnected-(U4-PB1-Pad19)") (class "Default")
      (node (ref "U4") (pin "19") (pinfunction "PB1_19") (pintype "bidirectional+no_connect"))
    )
    (net (code "82") (name "unconnected-(U4-PB2{slash}BOOT1-Pad20)") (class "Default")
      (node (ref "U4") (pin "20") (pinfunction "PB2/BOOT1_20") (pintype "bidirectional+no_connect"))
    )
    (net (code "83") (name "unconnected-(U4-PB3-Pad39)") (class "Default")
      (node (ref "U4") (pin "39") (pinfunction "PB3_39") (pintype "bidirectional+no_connect"))
    )
    (net (code "84") (name "unconnected-(U4-PB4{slash}JNTRST-Pad40)") (class "Default")
      (node (ref "U4") (pin "40") (pinfunction "PB4/JNTRST_40") (pintype "bidirectional+no_connect"))
    )
    (net (code "85") (name "unconnected-(U4-PB8-Pad45)") (class "Default")
      (node (ref "U4") (pin "45") (pinfunction "PB8_45") (pintype "bidirectional+no_connect"))
    )
    (net (code "86") (name "unconnected-(U4-PB9-Pad46)") (class "Default")
      (node (ref "U4") (pin "46") (pinfunction "PB9_46") (pintype "bidirectional+no_connect"))
    )
    (net (code "87") (name "unconnected-(U4-PB10-Pad21)") (class "Default")
      (node (ref "U4") (pin "21") (pinfunction "PB10_21") (pintype "bidirectional"))
    )
    (net (code "88") (name "unconnected-(U4-PB11-Pad22)") (class "Default")
      (node (ref "U4") (pin "22") (pinfunction "PB11_22") (pintype "bidirectional"))
    )
    (net (code "89") (name "unconnected-(U4-PB13-Pad26)") (class "Default")
      (node (ref "U4") (pin "26") (pinfunction "PB13_26") (pintype "bidirectional+no_connect"))
    )
    (net (code "90") (name "unconnected-(U4-PB14-Pad27)") (class "Default")
      (node (ref "U4") (pin "27") (pinfunction "PB14_27") (pintype "bidirectional+no_connect"))
    )
    (net (code "91") (name "unconnected-(U4-PB15-Pad28)") (class "Default")
      (node (ref "U4") (pin "28") (pinfunction "PB15_28") (pintype "bidirectional+no_connect"))
    )
    (net (code "92") (name "unconnected-(U4-PC14-OSC32_IN-Pad3)") (class "Default")
      (node (ref "U4") (pin "3") (pinfunction "PC14-OSC32_IN_3") (pintype "bidirectional+no_connect"))
    )
    (net (code "93") (name "unconnected-(U4-PC15-OSC32_OUT-Pad4)") (class "Default")
      (node (ref "U4") (pin "4") (pinfunction "PC15-OSC32_OUT_4") (pintype "bidirectional+no_connect"))
    )
    (net (code "94") (name "unconnected-(U4-VBAT-Pad1)") (class "Default")
      (node (ref "U4") (pin "1") (pinfunction "VBAT_1") (pintype "power_in+no_connect"))
    )
  )
)
